# 04_Mcu.net
KiCad netlist of a schematic drawn in Altium Designer
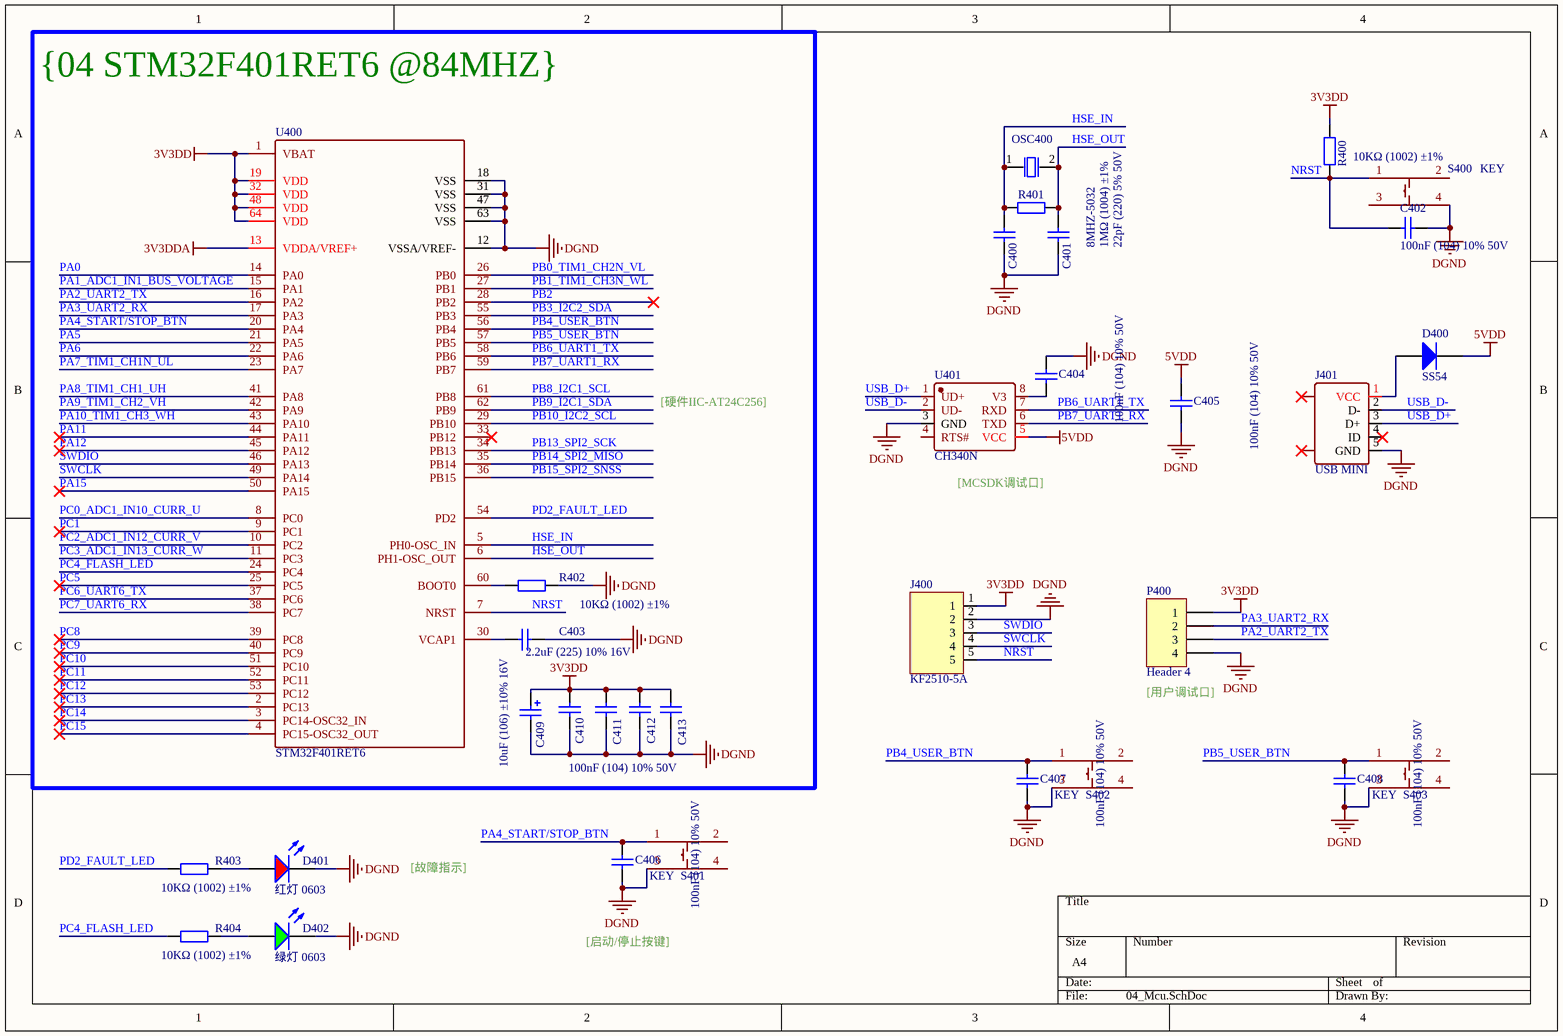
[diagram p0: 04_Mcu.SchDoc]

(export (version "E")
  (design (tool "Eeschema 10.0.6"))
  (components
    (comp (ref "C400")
      (value "22pF (220) 5% 50V")
      (footprint "LC-0603_C")
      (description "贴片电容")
      (libsource (lib "Miscellaneous Devices LC") (part "0603 22pF (220) 5% 50V"))
    )
    (comp (ref "C401")
      (value "22pF (220) 5% 50V")
      (footprint "LC-0603_C")
      (description "贴片电容")
      (libsource (lib "Miscellaneous Devices LC") (part "0603 22pF (220) 5% 50V"))
    )
    (comp (ref "C402")
      (value "100nF (104) 10% 50V")
      (footprint "LC-0603_C")
      (description "贴片电容")
      (libsource (lib "Miscellaneous Devices LC") (part "0603 100nF (104) 10% 50V"))
    )
    (comp (ref "C403")
      (value "2.2uF (225) 10% 16V")
      (footprint "LC-0603_C")
      (description "贴片电容")
      (libsource (lib "Miscellaneous Devices LC") (part "0603 2.2uF (225) 10% 16V"))
    )
    (comp (ref "C404")
      (value "100nF (104) 10% 50V")
      (footprint "LC-0603_C")
      (description "贴片电容")
      (libsource (lib "Miscellaneous Devices LC") (part "0603 100nF (104) 10% 50V"))
    )
    (comp (ref "C405")
      (value "100nF (104) 10% 50V")
      (footprint "LC-0603_C")
      (description "贴片电容")
      (libsource (lib "Miscellaneous Devices LC") (part "0603 100nF (104) 10% 50V"))
    )
    (comp (ref "C406")
      (value "100nF (104) 10% 50V")
      (footprint "LC-0603_C")
      (description "贴片电容")
      (libsource (lib "Miscellaneous Devices LC") (part "0603 100nF (104) 10% 50V"))
    )
    (comp (ref "C407")
      (value "100nF (104) 10% 50V")
      (footprint "LC-0603_C")
      (description "贴片电容")
      (libsource (lib "Miscellaneous Devices LC") (part "0603 100nF (104) 10% 50V"))
    )
    (comp (ref "C408")
      (value "100nF (104) 10% 50V")
      (footprint "LC-0603_C")
      (description "贴片电容")
      (libsource (lib "Miscellaneous Devices LC") (part "0603 100nF (104) 10% 50V"))
    )
    (comp (ref "C409")
      (value "10uF (106) ±10% 16V")
      (footprint "LC-CASE-A_3216")
      (description "钽电容")
      (libsource (lib "Miscellaneous Devices LC") (part "3216 10uF (106) 10% 16V"))
    )
    (comp (ref "C410")
      (value "100nF (104) 10% 50V")
      (footprint "LC-0603_C")
      (description "贴片电容")
      (libsource (lib "Miscellaneous Devices LC") (part "0603 100nF (104) 10% 50V"))
    )
    (comp (ref "C411")
      (value "100nF (104) 10% 50V")
      (footprint "LC-0603_C")
      (description "贴片电容")
      (libsource (lib "Miscellaneous Devices LC") (part "0603 100nF (104) 10% 50V"))
    )
    (comp (ref "C412")
      (value "100nF (104) 10% 50V")
      (footprint "LC-0603_C")
      (description "贴片电容")
      (libsource (lib "Miscellaneous Devices LC") (part "0603 100nF (104) 10% 50V"))
    )
    (comp (ref "C413")
      (value "100nF (104) 10% 50V")
      (footprint "LC-0603_C")
      (description "贴片电容")
      (libsource (lib "Miscellaneous Devices LC") (part "0603 100nF (104) 10% 50V"))
    )
    (comp (ref "D400")
      (value "SS54")
      (footprint "SS54")
      (description "二极管")
      (libsource (lib "Miscellaneous Devices LC") (part "SMA(DO-214AC) SS54"))
    )
    (comp (ref "D401")
      (value "红灯 0603")
      (footprint "LC-0603_LED_S1")
      (description "发光二极管")
      (libsource (lib "Miscellaneous Devices LC") (part "0603 红灯"))
    )
    (comp (ref "D402")
      (value "绿灯 0603")
      (footprint "LC-0603_LED_S1")
      (description "发光二极管")
      (libsource (lib "Miscellaneous Devices LC") (part "0603 绿灯"))
    )
    (comp (ref "J400")
      (value "KF2510-5A")
      (footprint "KF2510-5A")
      (libsource (lib "Schlibv2") (part "KF2510-5A"))
    )
    (comp (ref "J401")
      (value "USB MINI")
      (footprint "USB_MINI")
      (libsource (lib "Schlibv2") (part "USB MINI"))
    )
    (comp (ref "OSC400")
      (value "8MHZ-5032")
      (footprint "8MHZ-5032")
      (libsource (lib "Schlibv2") (part "8MHZ-5032"))
    )
    (comp (ref "P400")
      (value "Header 4")
      (footprint "2.54_4P_PIN")
      (description "Header, 4-Pin")
      (fields (field (name "PUBLISHER") "Altium Limited"))
      (libsource (lib "Miscellaneous Connectors") (part "Header 4"))
    )
    (comp (ref "R400")
      (value "10KΩ (1002) ±1%")
      (footprint "LC-0603_R")
      (description "贴片电阻")
      (libsource (lib "") (part "0603 10KΩ (1002) 1%_1"))
    )
    (comp (ref "R401")
      (value "1MΩ (1004) ±1%")
      (footprint "LC-0603_R")
      (description "贴片电阻")
      (libsource (lib "Miscellaneous Devices LC") (part "0603 1MΩ (1004) 1%"))
    )
    (comp (ref "R402")
      (value "10KΩ (1002) ±1%")
      (footprint "LC-0603_R")
      (description "贴片电阻")
      (libsource (lib "Miscellaneous Devices LC") (part "0603 10KΩ (1002) 1%"))
    )
    (comp (ref "R403")
      (value "10KΩ (1002) ±1%")
      (footprint "LC-0603_R")
      (description "贴片电阻")
      (libsource (lib "Miscellaneous Devices LC") (part "0603 10KΩ (1002) 1%"))
    )
    (comp (ref "R404")
      (value "10KΩ (1002) ±1%")
      (footprint "LC-0603_R")
      (description "贴片电阻")
      (libsource (lib "Miscellaneous Devices LC") (part "0603 10KΩ (1002) 1%"))
    )
    (comp (ref "S400")
      (value "KEY")
      (footprint "KEY_WHITE")
      (description "白色方块")
      (libsource (lib "Schlibv2") (part "KEY"))
    )
    (comp (ref "S401")
      (value "KEY")
      (footprint "KEY_WHITE")
      (description "白色方块")
      (libsource (lib "Schlibv2") (part "KEY"))
    )
    (comp (ref "S402")
      (value "KEY")
      (footprint "KEY_WHITE")
      (description "白色方块")
      (libsource (lib "Schlibv2") (part "KEY"))
    )
    (comp (ref "S403")
      (value "KEY")
      (footprint "KEY_WHITE")
      (description "白色方块")
      (libsource (lib "Schlibv2") (part "KEY"))
    )
    (comp (ref "U400")
      (value "STM32F401RET6")
      (footprint "STM32F401RET6")
      (libsource (lib "Schlibv2") (part "STM32F401RET6"))
    )
    (comp (ref "U401") (value "CH340N") (footprint "CH340N") (libsource (lib "Schlibv2") (part "CH340N")))
  )
  (nets
    (net (code "1") (name "/HSE_IN") (class "Default")
      (node (ref "C400") (pin "2") (pinfunction "2_2") (pintype "passive"))
      (node (ref "OSC400") (pin "1") (pinfunction "OSC1_1") (pintype "passive"))
      (node (ref "R401") (pin "1") (pinfunction "1_1") (pintype "passive"))
      (node (ref "U400") (pin "5") (pinfunction "PH0-OSC_IN_5") (pintype "passive"))
    )
    (net (code "2") (name "/HSE_OUT") (class "Default")
      (node (ref "C401") (pin "2") (pinfunction "2_2") (pintype "passive"))
      (node (ref "OSC400") (pin "2") (pinfunction "OSC2_2") (pintype "passive"))
      (node (ref "R401") (pin "2") (pinfunction "2_2") (pintype "passive"))
      (node (ref "U400") (pin "6") (pinfunction "PH1-OSC_OUT_6") (pintype "passive"))
    )
    (net (code "3") (name "/NRST") (class "Default")
      (node (ref "C402") (pin "2") (pinfunction "2_2") (pintype "passive"))
      (node (ref "J400") (pin "5") (pinfunction "5_5") (pintype "passive"))
      (node (ref "R400") (pin "1") (pinfunction "1_1") (pintype "passive"))
      (node (ref "S400") (pin "1") (pinfunction "1_1") (pintype "passive"))
      (node (ref "U400") (pin "7") (pinfunction "NRST_7") (pintype "passive"))
    )
    (net (code "4") (name "/PA0") (class "Default")
      (node (ref "U400") (pin "14") (pinfunction "PA0_14") (pintype "passive"))
    )
    (net (code "5") (name "/PA1_ADC1_IN1_BUS_VOLTAGE") (class "Default")
      (node (ref "U400") (pin "15") (pinfunction "PA1_15") (pintype "passive"))
    )
    (net (code "6") (name "/PA2_UART2_TX") (class "Default")
      (node (ref "P400") (pin "3") (pinfunction "3_3") (pintype "passive"))
      (node (ref "U400") (pin "16") (pinfunction "PA2_16") (pintype "passive"))
    )
    (net (code "7") (name "/PA3_UART2_RX") (class "Default")
      (node (ref "P400") (pin "2") (pinfunction "2_2") (pintype "passive"))
      (node (ref "U400") (pin "17") (pinfunction "PA3_17") (pintype "passive"))
    )
    (net (code "8") (name "/PA4_START{slash}STOP_BTN") (class "Default")
      (node (ref "C406") (pin "2") (pinfunction "2_2") (pintype "passive"))
      (node (ref "S401") (pin "1") (pinfunction "1_1") (pintype "passive"))
      (node (ref "U400") (pin "20") (pinfunction "PA4_20") (pintype "passive"))
    )
    (net (code "9") (name "/PA5") (class "Default")
      (node (ref "U400") (pin "21") (pinfunction "PA5_21") (pintype "passive"))
    )
    (net (code "10") (name "/PA6") (class "Default")
      (node (ref "U400") (pin "22") (pinfunction "PA6_22") (pintype "passive"))
    )
    (net (code "11") (name "/PA7_TIM1_CH1N_UL") (class "Default")
      (node (ref "U400") (pin "23") (pinfunction "PA7_23") (pintype "passive"))
    )
    (net (code "12") (name "/PA8_TIM1_CH1_UH") (class "Default")
      (node (ref "U400") (pin "41") (pinfunction "PA8_41") (pintype "passive"))
    )
    (net (code "13") (name "/PA9_TIM1_CH2_VH") (class "Default")
      (node (ref "U400") (pin "42") (pinfunction "PA9_42") (pintype "passive"))
    )
    (net (code "14") (name "/PA10_TIM1_CH3_WH") (class "Default")
      (node (ref "U400") (pin "43") (pinfunction "PA10_43") (pintype "passive"))
    )
    (net (code "15") (name "/PA11") (class "Default")
      (node (ref "U400") (pin "44") (pinfunction "PA11_44") (pintype "passive+no_connect"))
    )
    (net (code "16") (name "/PA12") (class "Default")
      (node (ref "U400") (pin "45") (pinfunction "PA12_45") (pintype "passive+no_connect"))
    )
    (net (code "17") (name "/PA15") (class "Default")
      (node (ref "U400") (pin "50") (pinfunction "PA15_50") (pintype "passive+no_connect"))
    )
    (net (code "18") (name "/PB0_TIM1_CH2N_VL") (class "Default")
      (node (ref "U400") (pin "26") (pinfunction "PB0_26") (pintype "passive"))
    )
    (net (code "19") (name "/PB1_TIM1_CH3N_WL") (class "Default")
      (node (ref "U400") (pin "27") (pinfunction "PB1_27") (pintype "passive"))
    )
    (net (code "20") (name "/PB2") (class "Default")
      (node (ref "U400") (pin "28") (pinfunction "PB2_28") (pintype "passive+no_connect"))
    )
    (net (code "21") (name "/PB3_I2C2_SDA") (class "Default")
      (node (ref "U400") (pin "55") (pinfunction "PB3_55") (pintype "passive"))
    )
    (net (code "22") (name "/PB4_USER_BTN") (class "Default")
      (node (ref "C407") (pin "2") (pinfunction "2_2") (pintype "passive"))
      (node (ref "S402") (pin "1") (pinfunction "1_1") (pintype "passive"))
      (node (ref "U400") (pin "56") (pinfunction "PB4_56") (pintype "passive"))
    )
    (net (code "23") (name "/PB5_USER_BTN") (class "Default")
      (node (ref "C408") (pin "2") (pinfunction "2_2") (pintype "passive"))
      (node (ref "S403") (pin "1") (pinfunction "1_1") (pintype "passive"))
      (node (ref "U400") (pin "57") (pinfunction "PB5_57") (pintype "passive"))
    )
    (net (code "24") (name "/PB6_UART1_TX") (class "Default")
      (node (ref "U400") (pin "58") (pinfunction "PB6_58") (pintype "passive"))
      (node (ref "U401") (pin "7") (pinfunction "RXD_7") (pintype "passive"))
    )
    (net (code "25") (name "/PB7_UART1_RX") (class "Default")
      (node (ref "U400") (pin "59") (pinfunction "PB7_59") (pintype "passive"))
      (node (ref "U401") (pin "6") (pinfunction "TXD_6") (pintype "passive"))
    )
    (net (code "26") (name "/PB8_I2C1_SCL") (class "Default")
      (node (ref "U400") (pin "61") (pinfunction "PB8_61") (pintype "passive"))
    )
    (net (code "27") (name "/PB9_I2C1_SDA") (class "Default")
      (node (ref "U400") (pin "62") (pinfunction "PB9_62") (pintype "passive"))
    )
    (net (code "28") (name "/PB10_I2C2_SCL") (class "Default")
      (node (ref "U400") (pin "29") (pinfunction "PB10_29") (pintype "passive"))
    )
    (net (code "29") (name "/PB13_SPI2_SCK") (class "Default")
      (node (ref "U400") (pin "34") (pinfunction "PB13_34") (pintype "passive"))
    )
    (net (code "30") (name "/PB14_SPI2_MISO") (class "Default")
      (node (ref "U400") (pin "35") (pinfunction "PB14_35") (pintype "passive"))
    )
    (net (code "31") (name "/PB15_SPI2_SNSS") (class "Default")
      (node (ref "U400") (pin "36") (pinfunction "PB15_36") (pintype "passive"))
    )
    (net (code "32") (name "/PC0_ADC1_IN10_CURR_U") (class "Default")
      (node (ref "U400") (pin "8") (pinfunction "PC0_8") (pintype "passive"))
    )
    (net (code "33") (name "/PC1") (class "Default")
      (node (ref "U400") (pin "9") (pinfunction "PC1_9") (pintype "passive+no_connect"))
    )
    (net (code "34") (name "/PC2_ADC1_IN12_CURR_V") (class "Default")
      (node (ref "U400") (pin "10") (pinfunction "PC2_10") (pintype "passive"))
    )
    (net (code "35") (name "/PC3_ADC1_IN13_CURR_W") (class "Default")
      (node (ref "U400") (pin "11") (pinfunction "PC3_11") (pintype "passive"))
    )
    (net (code "36") (name "/PC4_FLASH_LED") (class "Default")
      (node (ref "R404") (pin "1") (pinfunction "1_1") (pintype "passive"))
      (node (ref "U400") (pin "24") (pinfunction "PC4_24") (pintype "passive"))
    )
    (net (code "37") (name "/PC5") (class "Default")
      (node (ref "U400") (pin "25") (pinfunction "PC5_25") (pintype "passive+no_connect"))
    )
    (net (code "38") (name "/PC6_UART6_TX") (class "Default")
      (node (ref "U400") (pin "37") (pinfunction "PC6_37") (pintype "passive"))
    )
    (net (code "39") (name "/PC7_UART6_RX") (class "Default")
      (node (ref "U400") (pin "38") (pinfunction "PC7_38") (pintype "passive"))
    )
    (net (code "40") (name "/PC8") (class "Default")
      (node (ref "U400") (pin "39") (pinfunction "PC8_39") (pintype "passive+no_connect"))
    )
    (net (code "41") (name "/PC9") (class "Default")
      (node (ref "U400") (pin "40") (pinfunction "PC9_40") (pintype "passive+no_connect"))
    )
    (net (code "42") (name "/PC10") (class "Default")
      (node (ref "U400") (pin "51") (pinfunction "PC10_51") (pintype "passive+no_connect"))
    )
    (net (code "43") (name "/PC11") (class "Default")
      (node (ref "U400") (pin "52") (pinfunction "PC11_52") (pintype "passive+no_connect"))
    )
    (net (code "44") (name "/PC12") (class "Default")
      (node (ref "U400") (pin "53") (pinfunction "PC12_53") (pintype "passive+no_connect"))
    )
    (net (code "45") (name "/PC13") (class "Default")
      (node (ref "U400") (pin "2") (pinfunction "PC13_2") (pintype "passive+no_connect"))
    )
    (net (code "46") (name "/PC14") (class "Default")
      (node (ref "U400") (pin "3") (pinfunction "PC14-OSC32_IN_3") (pintype "passive+no_connect"))
    )
    (net (code "47") (name "/PC15") (class "Default")
      (node (ref "U400") (pin "4") (pinfunction "PC15-OSC32_OUT_4") (pintype "passive+no_connect"))
    )
    (net (code "48") (name "/PD2_FAULT_LED") (class "Default")
      (node (ref "R403") (pin "1") (pinfunction "1_1") (pintype "passive"))
      (node (ref "U400") (pin "54") (pinfunction "PD2_54") (pintype "passive"))
    )
    (net (code "49") (name "/SWCLK") (class "Default")
      (node (ref "J400") (pin "4") (pinfunction "4_4") (pintype "passive"))
      (node (ref "U400") (pin "49") (pinfunction "PA14_49") (pintype "passive"))
    )
    (net (code "50") (name "/SWDIO") (class "Default")
      (node (ref "J400") (pin "3") (pinfunction "3_3") (pintype "passive"))
      (node (ref "U400") (pin "46") (pinfunction "PA13_46") (pintype "passive"))
    )
    (net (code "51") (name "/USB_D+") (class "Default")
      (node (ref "J401") (pin "3") (pinfunction "D+_3") (pintype "passive"))
      (node (ref "U401") (pin "1") (pinfunction "UD+_1") (pintype "passive"))
    )
    (net (code "52") (name "/USB_D-") (class "Default")
      (node (ref "J401") (pin "2") (pinfunction "D-_2") (pintype "passive"))
      (node (ref "U401") (pin "2") (pinfunction "UD-_2") (pintype "passive"))
    )
    (net (code "53") (name "3V3DD") (class "Default")
      (node (ref "C409") (pin "1") (pinfunction "1_1") (pintype "passive"))
      (node (ref "C410") (pin "2") (pinfunction "2_2") (pintype "passive"))
      (node (ref "C411") (pin "2") (pinfunction "2_2") (pintype "passive"))
      (node (ref "C412") (pin "2") (pinfunction "2_2") (pintype "passive"))
      (node (ref "C413") (pin "2") (pinfunction "2_2") (pintype "passive"))
      (node (ref "J400") (pin "1") (pinfunction "1_1") (pintype "passive"))
      (node (ref "P400") (pin "1") (pinfunction "1_1") (pintype "passive"))
      (node (ref "R400") (pin "2") (pinfunction "2_2") (pintype "passive"))
      (node (ref "U400") (pin "1") (pinfunction "VBAT_1") (pintype "passive"))
      (node (ref "U400") (pin "19") (pinfunction "VDD_19") (pintype "passive"))
      (node (ref "U400") (pin "32") (pinfunction "VDD_32") (pintype "passive"))
      (node (ref "U400") (pin "48") (pinfunction "VDD_48") (pintype "passive"))
      (node (ref "U400") (pin "64") (pinfunction "VDD_64") (pintype "passive"))
    )
    (net (code "54") (name "3V3DDA") (class "Default")
      (node (ref "U400") (pin "13") (pinfunction "VDDA/VREF+_13") (pintype "passive"))
    )
    (net (code "55") (name "5VDD") (class "Default")
      (node (ref "C405") (pin "2") (pinfunction "2_2") (pintype "passive"))
      (node (ref "D400") (pin "2") (pinfunction "K_2") (pintype "passive"))
      (node (ref "U401") (pin "5") (pinfunction "VCC_5") (pintype "passive"))
    )
    (net (code "56") (name "DGND") (class "Default")
      (node (ref "C400") (pin "1") (pinfunction "1_1") (pintype "passive"))
      (node (ref "C401") (pin "1") (pinfunction "1_1") (pintype "passive"))
      (node (ref "C402") (pin "1") (pinfunction "1_1") (pintype "passive"))
      (node (ref "C403") (pin "1") (pinfunction "1_1") (pintype "passive"))
      (node (ref "C404") (pin "2") (pinfunction "2_2") (pintype "passive"))
      (node (ref "C405") (pin "1") (pinfunction "1_1") (pintype "passive"))
      (node (ref "C406") (pin "1") (pinfunction "1_1") (pintype "passive"))
      (node (ref "C407") (pin "1") (pinfunction "1_1") (pintype "passive"))
      (node (ref "C408") (pin "1") (pinfunction "1_1") (pintype "passive"))
      (node (ref "C409") (pin "2") (pinfunction "2_2") (pintype "passive"))
      (node (ref "C410") (pin "1") (pinfunction "1_1") (pintype "passive"))
      (node (ref "C411") (pin "1") (pinfunction "1_1") (pintype "passive"))
      (node (ref "C412") (pin "1") (pinfunction "1_1") (pintype "passive"))
      (node (ref "C413") (pin "1") (pinfunction "1_1") (pintype "passive"))
      (node (ref "D401") (pin "K") (pinfunction "K_K") (pintype "passive"))
      (node (ref "D402") (pin "K") (pinfunction "K_K") (pintype "passive"))
      (node (ref "J400") (pin "2") (pinfunction "2_2") (pintype "passive"))
      (node (ref "J401") (pin "5") (pinfunction "GND_5") (pintype "passive"))
      (node (ref "P400") (pin "4") (pinfunction "4_4") (pintype "passive"))
      (node (ref "R402") (pin "2") (pinfunction "2_2") (pintype "passive"))
      (node (ref "S400") (pin "4") (pinfunction "4_4") (pintype "passive"))
      (node (ref "S401") (pin "3") (pinfunction "3_3") (pintype "passive"))
      (node (ref "S402") (pin "3") (pinfunction "3_3") (pintype "passive"))
      (node (ref "S403") (pin "3") (pinfunction "3_3") (pintype "passive"))
      (node (ref "U400") (pin "12") (pinfunction "VSSA/VREF-_12") (pintype "passive"))
      (node (ref "U400") (pin "18") (pinfunction "VSS_18") (pintype "passive"))
      (node (ref "U400") (pin "31") (pinfunction "VSS_31") (pintype "passive"))
      (node (ref "U400") (pin "47") (pinfunction "VSS_47") (pintype "passive"))
      (node (ref "U400") (pin "63") (pinfunction "VSS_63") (pintype "passive"))
      (node (ref "U401") (pin "3") (pinfunction "GND_3") (pintype "passive"))
    )
    (net (code "57") (name "Net-(D400-A)") (class "Default")
      (node (ref "D400") (pin "1") (pinfunction "A_1") (pintype "passive"))
      (node (ref "J401") (pin "1") (pinfunction "VCC_1") (pintype "passive"))
    )
    (net (code "58") (name "Net-(D401-PadA)") (class "Default")
      (node (ref "D401") (pin "A") (pinfunction "A_A") (pintype "passive"))
      (node (ref "R403") (pin "2") (pinfunction "2_2") (pintype "passive"))
    )
    (net (code "59") (name "Net-(D402-PadA)") (class "Default")
      (node (ref "D402") (pin "A") (pinfunction "A_A") (pintype "passive"))
      (node (ref "R404") (pin "2") (pinfunction "2_2") (pintype "passive"))
    )
    (net (code "60") (name "Net-(U400-BOOT0)") (class "Default")
      (node (ref "R402") (pin "1") (pinfunction "1_1") (pintype "passive"))
      (node (ref "U400") (pin "60") (pinfunction "BOOT0_60") (pintype "passive"))
    )
    (net (code "61") (name "Net-(U400-VCAP1)") (class "Default")
      (node (ref "C403") (pin "2") (pinfunction "2_2") (pintype "passive"))
      (node (ref "U400") (pin "30") (pinfunction "VCAP1_30") (pintype "passive"))
    )
    (net (code "62") (name "Net-(U401-V3)") (class "Default")
      (node (ref "C404") (pin "1") (pinfunction "1_1") (pintype "passive"))
      (node (ref "U401") (pin "8") (pinfunction "V3_8") (pintype "passive"))
    )
    (net (code "63") (name "unconnected-(J401-ID-Pad4)") (class "Default")
      (node (ref "J401") (pin "4") (pinfunction "ID_4") (pintype "passive+no_connect"))
    )
    (net (code "64") (name "unconnected-(J401-Pad0)") (class "Default")
      (node (ref "J401") (pin "0") (pinfunction "0_0") (pintype "passive+no_connect"))
    )
    (net (code "65") (name "unconnected-(J401-Pad0)_1") (class "Default")
      (node (ref "J401") (pin "0") (pinfunction "0_0") (pintype "passive+no_connect"))
    )
    (net (code "66") (name "unconnected-(S400-Pad2)") (class "Default")
      (node (ref "S400") (pin "2") (pinfunction "2_2") (pintype "passive"))
    )
    (net (code "67") (name "unconnected-(S400-Pad3)") (class "Default")
      (node (ref "S400") (pin "3") (pinfunction "3_3") (pintype "passive"))
    )
    (net (code "68") (name "unconnected-(S401-Pad2)") (class "Default")
      (node (ref "S401") (pin "2") (pinfunction "2_2") (pintype "passive"))
    )
    (net (code "69") (name "unconnected-(S401-Pad4)") (class "Default")
      (node (ref "S401") (pin "4") (pinfunction "4_4") (pintype "passive"))
    )
    (net (code "70") (name "unconnected-(S402-Pad2)") (class "Default")
      (node (ref "S402") (pin "2") (pinfunction "2_2") (pintype "passive"))
    )
    (net (code "71") (name "unconnected-(S402-Pad4)") (class "Default")
      (node (ref "S402") (pin "4") (pinfunction "4_4") (pintype "passive"))
    )
    (net (code "72") (name "unconnected-(S403-Pad2)") (class "Default")
      (node (ref "S403") (pin "2") (pinfunction "2_2") (pintype "passive"))
    )
    (net (code "73") (name "unconnected-(S403-Pad4)") (class "Default")
      (node (ref "S403") (pin "4") (pinfunction "4_4") (pintype "passive"))
    )
    (net (code "74") (name "unconnected-(U400-PB12-Pad33)") (class "Default")
      (node (ref "U400") (pin "33") (pinfunction "PB12_33") (pintype "passive+no_connect"))
    )
    (net (code "75") (name "unconnected-(U401-RTS#-Pad4)") (class "Default")
      (node (ref "U401") (pin "4") (pinfunction "RTS#_4") (pintype "passive"))
    )
  )
)
